# nusense-rs485.net
KiCad netlist of a schematic drawn in Altium Designer
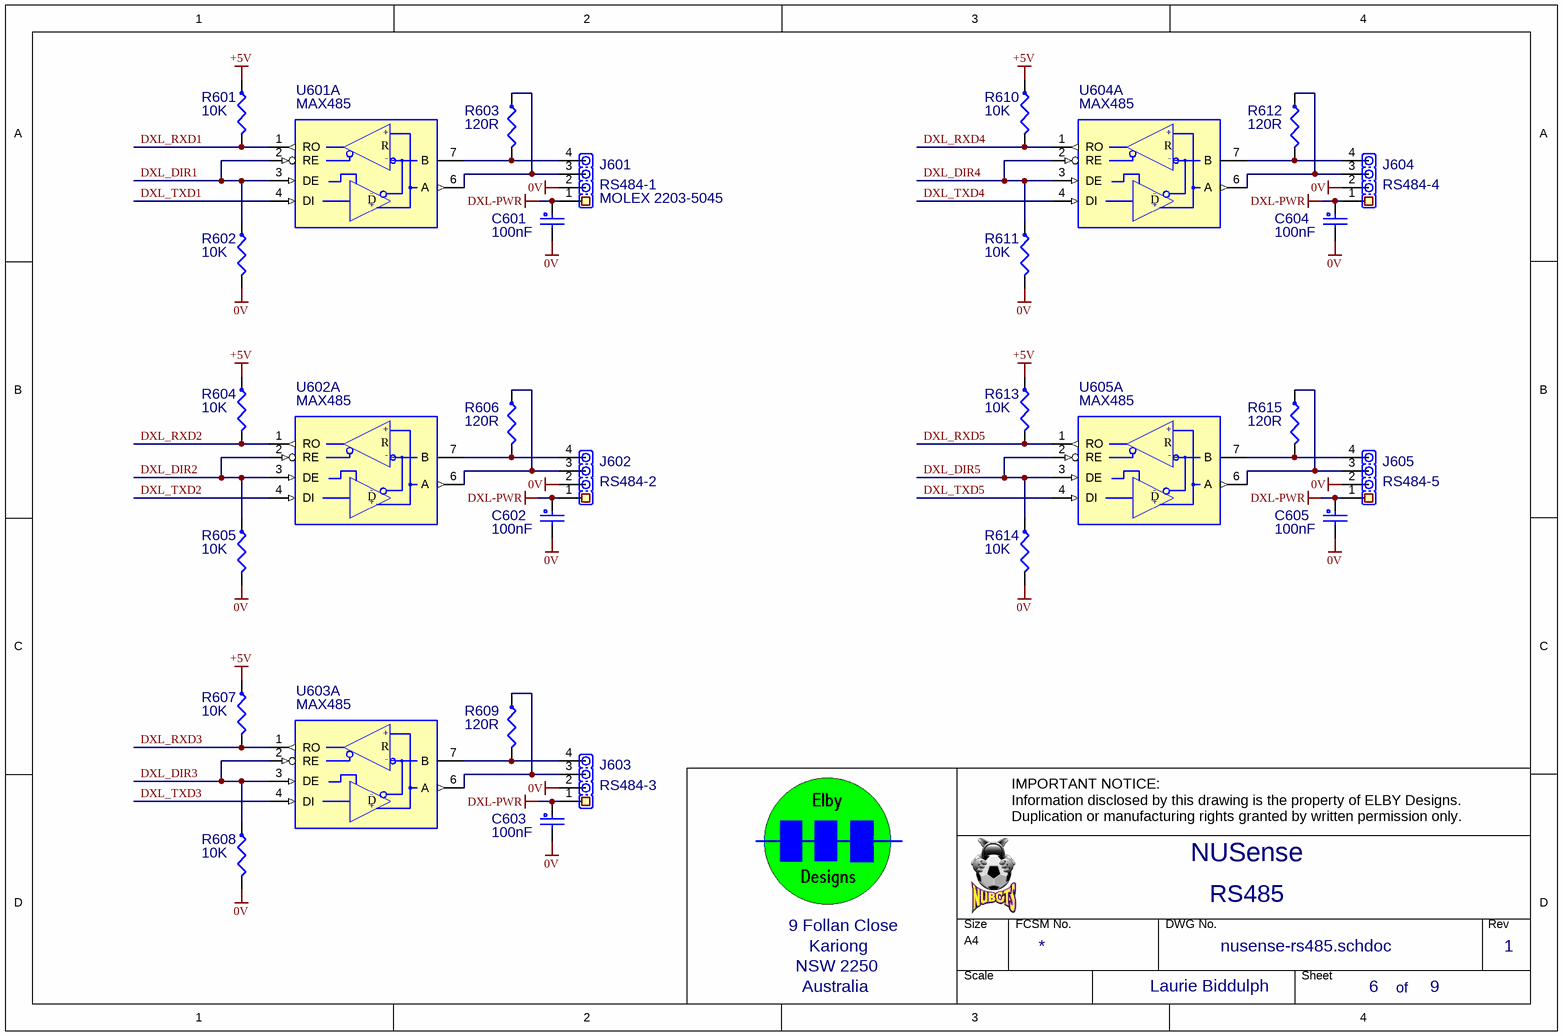
[diagram p0: nusense-rs485.schdoc]

(export (version "E")
  (design (tool "Eeschema 10.0.6"))
  (components
    (comp (ref "C601")
      (value "100nF")
      (footprint "RAD-0.2N(LB)")
      (description "Monolithic Ceramic")
      (libsource (lib "capacitor") (part "CC-100NF(LB)"))
    )
    (comp (ref "C602")
      (value "100nF")
      (footprint "RAD-0.2N(LB)")
      (description "Monolithic Ceramic")
      (libsource (lib "capacitor") (part "CC-100NF(LB)"))
    )
    (comp (ref "C603")
      (value "100nF")
      (footprint "RAD-0.2N(LB)")
      (description "Monolithic Ceramic")
      (libsource (lib "capacitor") (part "CC-100NF(LB)"))
    )
    (comp (ref "C604")
      (value "100nF")
      (footprint "RAD-0.2N(LB)")
      (description "Monolithic Ceramic")
      (libsource (lib "capacitor") (part "CC-100NF(LB)"))
    )
    (comp (ref "C605")
      (value "100nF")
      (footprint "RAD-0.2N(LB)")
      (description "Monolithic Ceramic")
      (libsource (lib "capacitor") (part "CC-100NF(LB)"))
    )
    (comp (ref "J601")
      (value "RS484-1")
      (footprint "HDR1X4(LB)")
      (description "1x4 Header")
      (fields (field (name "PART") "MOLEX 2203-5045"))
      (libsource (lib "connectors") (part "HEADER-1X4"))
    )
    (comp (ref "J602")
      (value "RS484-2")
      (footprint "HDR1X4(LB)")
      (description "1x4 Header")
      (libsource (lib "connectors") (part "HEADER-1X4"))
    )
    (comp (ref "J603")
      (value "RS484-3")
      (footprint "HDR1X4(LB)")
      (description "1x4 Header")
      (libsource (lib "connectors") (part "HEADER-1X4"))
    )
    (comp (ref "J604")
      (value "RS484-4")
      (footprint "HDR1X4(LB)")
      (description "1x4 Header")
      (libsource (lib "connectors") (part "HEADER-1X4"))
    )
    (comp (ref "J605")
      (value "RS484-5")
      (footprint "HDR1X4(LB)")
      (description "1x4 Header")
      (libsource (lib "connectors") (part "HEADER-1X4"))
    )
    (comp (ref "R601")
      (value "10K")
      (footprint "AXIAL-0.4(LB)")
      (description "0.5W 1% Metal Film Resistor")
      (libsource (lib "resistor") (part "RM-10K(LB)"))
    )
    (comp (ref "R602")
      (value "10K")
      (footprint "AXIAL-0.4(LB)")
      (description "0.5W 1% Metal Film Resistor")
      (libsource (lib "resistor") (part "RM-10K(LB)"))
    )
    (comp (ref "R603")
      (value "120R")
      (footprint "AXIAL-0.4(LB)")
      (description "0.5W 1% Metal Film Resistor")
      (libsource (lib "resistor") (part "RM-120R(LB)"))
    )
    (comp (ref "R604")
      (value "10K")
      (footprint "AXIAL-0.4(LB)")
      (description "0.5W 1% Metal Film Resistor")
      (libsource (lib "resistor") (part "RM-10K(LB)"))
    )
    (comp (ref "R605")
      (value "10K")
      (footprint "AXIAL-0.4(LB)")
      (description "0.5W 1% Metal Film Resistor")
      (libsource (lib "resistor") (part "RM-10K(LB)"))
    )
    (comp (ref "R606")
      (value "120R")
      (footprint "AXIAL-0.4(LB)")
      (description "0.5W 1% Metal Film Resistor")
      (libsource (lib "resistor") (part "RM-120R(LB)"))
    )
    (comp (ref "R607")
      (value "10K")
      (footprint "AXIAL-0.4(LB)")
      (description "0.5W 1% Metal Film Resistor")
      (libsource (lib "resistor") (part "RM-10K(LB)"))
    )
    (comp (ref "R608")
      (value "10K")
      (footprint "AXIAL-0.4(LB)")
      (description "0.5W 1% Metal Film Resistor")
      (libsource (lib "resistor") (part "RM-10K(LB)"))
    )
    (comp (ref "R609")
      (value "120R")
      (footprint "AXIAL-0.4(LB)")
      (description "0.5W 1% Metal Film Resistor")
      (libsource (lib "resistor") (part "RM-120R(LB)"))
    )
    (comp (ref "R610")
      (value "10K")
      (footprint "AXIAL-0.4(LB)")
      (description "0.5W 1% Metal Film Resistor")
      (libsource (lib "resistor") (part "RM-10K(LB)"))
    )
    (comp (ref "R611")
      (value "10K")
      (footprint "AXIAL-0.4(LB)")
      (description "0.5W 1% Metal Film Resistor")
      (libsource (lib "resistor") (part "RM-10K(LB)"))
    )
    (comp (ref "R612")
      (value "120R")
      (footprint "AXIAL-0.4(LB)")
      (description "0.5W 1% Metal Film Resistor")
      (libsource (lib "resistor") (part "RM-120R(LB)"))
    )
    (comp (ref "R613")
      (value "10K")
      (footprint "AXIAL-0.4(LB)")
      (description "0.5W 1% Metal Film Resistor")
      (libsource (lib "resistor") (part "RM-10K(LB)"))
    )
    (comp (ref "R614")
      (value "10K")
      (footprint "AXIAL-0.4(LB)")
      (description "0.5W 1% Metal Film Resistor")
      (libsource (lib "resistor") (part "RM-10K(LB)"))
    )
    (comp (ref "R615")
      (value "120R")
      (footprint "AXIAL-0.4(LB)")
      (description "0.5W 1% Metal Film Resistor")
      (libsource (lib "resistor") (part "RM-120R(LB)"))
    )
    (comp (ref "U601")
      (value "MAX485")
      (footprint "DIP-8(LB)")
      (description "Low-power, Slew-rate limited RS485/RS422 Transceiver")
      (libsource (lib "ic") (part "MAX485(LB)"))
    )
    (comp (ref "U602")
      (value "MAX485")
      (footprint "DIP-8(LB)")
      (description "Low-power, Slew-rate limited RS485/RS422 Transceiver")
      (libsource (lib "ic") (part "MAX485(LB)"))
    )
    (comp (ref "U603")
      (value "MAX485")
      (footprint "DIP-8(LB)")
      (description "Low-power, Slew-rate limited RS485/RS422 Transceiver")
      (libsource (lib "ic") (part "MAX485(LB)"))
    )
    (comp (ref "U604")
      (value "MAX485")
      (footprint "DIP-8(LB)")
      (description "Low-power, Slew-rate limited RS485/RS422 Transceiver")
      (libsource (lib "ic") (part "MAX485(LB)"))
    )
    (comp (ref "U605")
      (value "MAX485")
      (footprint "DIP-8(LB)")
      (description "Low-power, Slew-rate limited RS485/RS422 Transceiver")
      (libsource (lib "ic") (part "MAX485(LB)"))
    )
  )
  (nets
    (net (code "1") (name "+5V") (class "Default")
      (node (ref "R601") (pin "1") (pinfunction "1_1") (pintype "passive"))
      (node (ref "R604") (pin "1") (pinfunction "1_1") (pintype "passive"))
      (node (ref "R607") (pin "1") (pinfunction "1_1") (pintype "passive"))
      (node (ref "R610") (pin "1") (pinfunction "1_1") (pintype "passive"))
      (node (ref "R613") (pin "1") (pinfunction "1_1") (pintype "passive"))
    )
    (net (code "2") (name "/DXL_DIR1") (class "Default")
      (node (ref "R602") (pin "1") (pinfunction "1_1") (pintype "passive"))
      (node (ref "U601") (pin "2") (pinfunction "RE_2") (pintype "input"))
      (node (ref "U601") (pin "3") (pinfunction "DE_3") (pintype "input"))
    )
    (net (code "3") (name "/DXL_DIR2") (class "Default")
      (node (ref "R605") (pin "1") (pinfunction "1_1") (pintype "passive"))
      (node (ref "U602") (pin "2") (pinfunction "RE_2") (pintype "input"))
      (node (ref "U602") (pin "3") (pinfunction "DE_3") (pintype "input"))
    )
    (net (code "4") (name "/DXL_DIR3") (class "Default")
      (node (ref "R608") (pin "1") (pinfunction "1_1") (pintype "passive"))
      (node (ref "U603") (pin "2") (pinfunction "RE_2") (pintype "input"))
      (node (ref "U603") (pin "3") (pinfunction "DE_3") (pintype "input"))
    )
    (net (code "5") (name "/DXL_DIR4") (class "Default")
      (node (ref "R611") (pin "1") (pinfunction "1_1") (pintype "passive"))
      (node (ref "U604") (pin "2") (pinfunction "RE_2") (pintype "input"))
      (node (ref "U604") (pin "3") (pinfunction "DE_3") (pintype "input"))
    )
    (net (code "6") (name "/DXL_DIR5") (class "Default")
      (node (ref "R614") (pin "1") (pinfunction "1_1") (pintype "passive"))
      (node (ref "U605") (pin "2") (pinfunction "RE_2") (pintype "input"))
      (node (ref "U605") (pin "3") (pinfunction "DE_3") (pintype "input"))
    )
    (net (code "7") (name "/DXL_RXD1") (class "Default")
      (node (ref "R601") (pin "2") (pinfunction "2_2") (pintype "passive"))
      (node (ref "U601") (pin "1") (pinfunction "RO_1") (pintype "output"))
    )
    (net (code "8") (name "/DXL_RXD2") (class "Default")
      (node (ref "R604") (pin "2") (pinfunction "2_2") (pintype "passive"))
      (node (ref "U602") (pin "1") (pinfunction "RO_1") (pintype "output"))
    )
    (net (code "9") (name "/DXL_RXD3") (class "Default")
      (node (ref "R607") (pin "2") (pinfunction "2_2") (pintype "passive"))
      (node (ref "U603") (pin "1") (pinfunction "RO_1") (pintype "output"))
    )
    (net (code "10") (name "/DXL_RXD4") (class "Default")
      (node (ref "R610") (pin "2") (pinfunction "2_2") (pintype "passive"))
      (node (ref "U604") (pin "1") (pinfunction "RO_1") (pintype "output"))
    )
    (net (code "11") (name "/DXL_RXD5") (class "Default")
      (node (ref "R613") (pin "2") (pinfunction "2_2") (pintype "passive"))
      (node (ref "U605") (pin "1") (pinfunction "RO_1") (pintype "output"))
    )
    (net (code "12") (name "/DXL_TXD1") (class "Default")
      (node (ref "U601") (pin "4") (pinfunction "DI_4") (pintype "input"))
    )
    (net (code "13") (name "/DXL_TXD2") (class "Default")
      (node (ref "U602") (pin "4") (pinfunction "DI_4") (pintype "input"))
    )
    (net (code "14") (name "/DXL_TXD3") (class "Default")
      (node (ref "U603") (pin "4") (pinfunction "DI_4") (pintype "input"))
    )
    (net (code "15") (name "/DXL_TXD4") (class "Default")
      (node (ref "U604") (pin "4") (pinfunction "DI_4") (pintype "input"))
    )
    (net (code "16") (name "/DXL_TXD5") (class "Default")
      (node (ref "U605") (pin "4") (pinfunction "DI_4") (pintype "input"))
    )
    (net (code "17") (name "0V") (class "Default")
      (node (ref "C601") (pin "2") (pintype "passive"))
      (node (ref "C602") (pin "2") (pintype "passive"))
      (node (ref "C603") (pin "2") (pintype "passive"))
      (node (ref "C604") (pin "2") (pintype "passive"))
      (node (ref "C605") (pin "2") (pintype "passive"))
      (node (ref "J601") (pin "2") (pinfunction "2_2") (pintype "passive"))
      (node (ref "J602") (pin "2") (pinfunction "2_2") (pintype "passive"))
      (node (ref "J603") (pin "2") (pinfunction "2_2") (pintype "passive"))
      (node (ref "J604") (pin "2") (pinfunction "2_2") (pintype "passive"))
      (node (ref "J605") (pin "2") (pinfunction "2_2") (pintype "passive"))
      (node (ref "R602") (pin "2") (pinfunction "2_2") (pintype "passive"))
      (node (ref "R605") (pin "2") (pinfunction "2_2") (pintype "passive"))
      (node (ref "R608") (pin "2") (pinfunction "2_2") (pintype "passive"))
      (node (ref "R611") (pin "2") (pinfunction "2_2") (pintype "passive"))
      (node (ref "R614") (pin "2") (pinfunction "2_2") (pintype "passive"))
    )
    (net (code "18") (name "DXL-PWR") (class "Default")
      (node (ref "C601") (pin "1") (pintype "passive"))
      (node (ref "C602") (pin "1") (pintype "passive"))
      (node (ref "C603") (pin "1") (pintype "passive"))
      (node (ref "C604") (pin "1") (pintype "passive"))
      (node (ref "C605") (pin "1") (pintype "passive"))
      (node (ref "J601") (pin "1") (pinfunction "1_1") (pintype "passive"))
      (node (ref "J602") (pin "1") (pinfunction "1_1") (pintype "passive"))
      (node (ref "J603") (pin "1") (pinfunction "1_1") (pintype "passive"))
      (node (ref "J604") (pin "1") (pinfunction "1_1") (pintype "passive"))
      (node (ref "J605") (pin "1") (pinfunction "1_1") (pintype "passive"))
    )
    (net (code "19") (name "Net-(U601A-A)") (class "Default")
      (node (ref "J601") (pin "3") (pinfunction "3_3") (pintype "passive"))
      (node (ref "R603") (pin "1") (pinfunction "1_1") (pintype "passive"))
      (node (ref "U601") (pin "6") (pinfunction "A_6") (pintype "output"))
    )
    (net (code "20") (name "Net-(U601A-B)") (class "Default")
      (node (ref "J601") (pin "4") (pinfunction "4_4") (pintype "passive"))
      (node (ref "R603") (pin "2") (pinfunction "2_2") (pintype "passive"))
      (node (ref "U601") (pin "7") (pinfunction "B_7") (pintype "passive"))
    )
    (net (code "21") (name "Net-(U602A-A)") (class "Default")
      (node (ref "J602") (pin "3") (pinfunction "3_3") (pintype "passive"))
      (node (ref "R606") (pin "1") (pinfunction "1_1") (pintype "passive"))
      (node (ref "U602") (pin "6") (pinfunction "A_6") (pintype "output"))
    )
    (net (code "22") (name "Net-(U602A-B)") (class "Default")
      (node (ref "J602") (pin "4") (pinfunction "4_4") (pintype "passive"))
      (node (ref "R606") (pin "2") (pinfunction "2_2") (pintype "passive"))
      (node (ref "U602") (pin "7") (pinfunction "B_7") (pintype "passive"))
    )
    (net (code "23") (name "Net-(U603A-A)") (class "Default")
      (node (ref "J603") (pin "3") (pinfunction "3_3") (pintype "passive"))
      (node (ref "R609") (pin "1") (pinfunction "1_1") (pintype "passive"))
      (node (ref "U603") (pin "6") (pinfunction "A_6") (pintype "output"))
    )
    (net (code "24") (name "Net-(U603A-B)") (class "Default")
      (node (ref "J603") (pin "4") (pinfunction "4_4") (pintype "passive"))
      (node (ref "R609") (pin "2") (pinfunction "2_2") (pintype "passive"))
      (node (ref "U603") (pin "7") (pinfunction "B_7") (pintype "passive"))
    )
    (net (code "25") (name "Net-(U604A-A)") (class "Default")
      (node (ref "J604") (pin "3") (pinfunction "3_3") (pintype "passive"))
      (node (ref "R612") (pin "1") (pinfunction "1_1") (pintype "passive"))
      (node (ref "U604") (pin "6") (pinfunction "A_6") (pintype "output"))
    )
    (net (code "26") (name "Net-(U604A-B)") (class "Default")
      (node (ref "J604") (pin "4") (pinfunction "4_4") (pintype "passive"))
      (node (ref "R612") (pin "2") (pinfunction "2_2") (pintype "passive"))
      (node (ref "U604") (pin "7") (pinfunction "B_7") (pintype "passive"))
    )
    (net (code "27") (name "Net-(U605A-A)") (class "Default")
      (node (ref "J605") (pin "3") (pinfunction "3_3") (pintype "passive"))
      (node (ref "R615") (pin "1") (pinfunction "1_1") (pintype "passive"))
      (node (ref "U605") (pin "6") (pinfunction "A_6") (pintype "output"))
    )
    (net (code "28") (name "Net-(U605A-B)") (class "Default")
      (node (ref "J605") (pin "4") (pinfunction "4_4") (pintype "passive"))
      (node (ref "R615") (pin "2") (pinfunction "2_2") (pintype "passive"))
      (node (ref "U605") (pin "7") (pinfunction "B_7") (pintype "passive"))
    )
  )
)
